# bare_bone_arduino.net
KiCad netlist of a schematic drawn in EAGLE
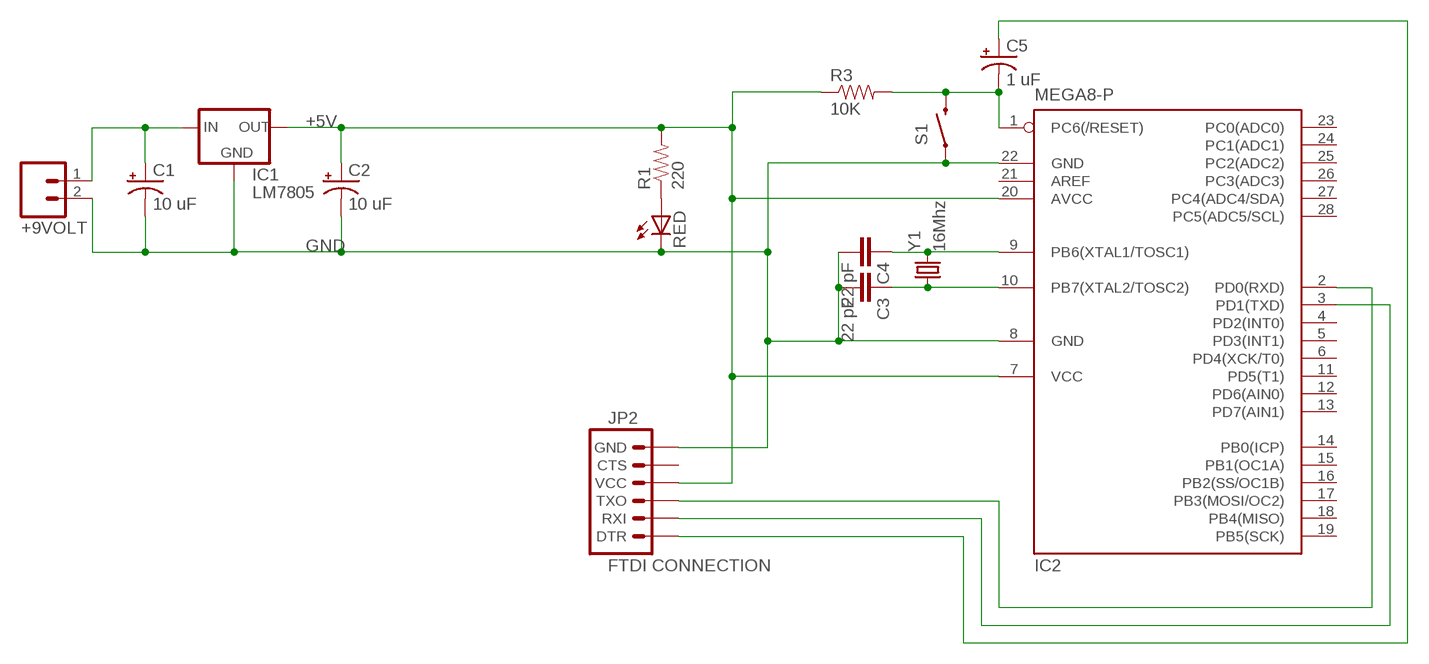
[diagram p0: schematic, sheet 1]

(export (version "E")
  (design (tool "Eeschema 10.0.6"))
  (components
    (comp (ref "+9VOLT")
      (value "M02PTH4")
      (footprint "eagle-import:1X02_XTRA_BIG")
      (libsource (lib "eagle-import") (part "M02PTH4"))
    )
    (comp (ref "C1")
      (value "10 uF")
      (footprint "eagle-import:VISHAY_C")
      (libsource (lib "eagle-import") (part "CAP_POLSMD"))
    )
    (comp (ref "C2")
      (value "10 uF")
      (footprint "eagle-import:VISHAY_C")
      (libsource (lib "eagle-import") (part "CAP_POLSMD"))
    )
    (comp (ref "C3")
      (value "22 pF")
      (footprint "eagle-import:CAP-PTH-5MM")
      (libsource (lib "eagle-import") (part "CAPPTH1"))
    )
    (comp (ref "C4")
      (value "22 pF")
      (footprint "eagle-import:CAP-PTH-5MM")
      (libsource (lib "eagle-import") (part "CAPPTH1"))
    )
    (comp (ref "C5")
      (value "1 uF")
      (footprint "eagle-import:CPOL-RADIAL-100UF-25V")
      (libsource (lib "eagle-import") (part "CAP_POLPTH1"))
    )
    (comp (ref "IC1")
      (value "LM7805")
      (footprint "eagle-import:TO-220-ALT")
      (libsource (lib "eagle-import") (part "V_REG_78XX-TO-220"))
    )
    (comp (ref "IC2")
      (value "MEGA8-P")
      (footprint "eagle-import:DIL28-3")
      (libsource (lib "eagle-import") (part "MEGA8-P"))
    )
    (comp (ref "JP2")
      (value "FTDI CONNECTION")
      (footprint "eagle-import:1X06")
      (libsource (lib "eagle-import") (part "ARDUINO_SERIAL_PROGRAMPTH"))
    )
    (comp (ref "R1")
      (value "220")
      (footprint "eagle-import:AXIAL-0.4")
      (libsource (lib "eagle-import") (part "RESISTORPTH-1/4W"))
    )
    (comp (ref "R3")
      (value "10K")
      (footprint "eagle-import:AXIAL-0.4")
      (libsource (lib "eagle-import") (part "RESISTORPTH-1/4W"))
    )
    (comp (ref "RED")
      (value "LED3MM")
      (footprint "eagle-import:LED3MM")
      (libsource (lib "eagle-import") (part "LED3MM"))
    )
    (comp (ref "S1")
      (value "SWITCH-MOMENTARY-2PTH")
      (footprint "eagle-import:TACTILE-PTH")
      (libsource (lib "eagle-import") (part "SWITCH-MOMENTARY-2PTH"))
    )
    (comp (ref "Y1")
      (value "16Mhz")
      (footprint "eagle-import:HC49US")
      (libsource (lib "eagle-import") (part "CRYSTALHC49US"))
    )
  )
  (nets
    (net (code "1") (name "/+5V") (class "Default")
      (node (ref "C2") (pin "+") (pinfunction "+_+") (pintype "passive"))
      (node (ref "IC1") (pin "OUT") (pinfunction "OUT_OUT") (pintype "output"))
      (node (ref "IC2") (pin "20") (pinfunction "AVCC_20") (pintype "power_in"))
      (node (ref "IC2") (pin "7") (pinfunction "VCC_7") (pintype "power_in"))
      (node (ref "JP2") (pin "4") (pinfunction "VCC_4") (pintype "passive"))
      (node (ref "R1") (pin "P$2") (pinfunction "2_P$2") (pintype "passive"))
      (node (ref "R3") (pin "P$1") (pinfunction "1_P$1") (pintype "passive"))
    )
    (net (code "2") (name "/GND") (class "Default")
      (node (ref "+9VOLT") (pin "2") (pinfunction "2_2") (pintype "passive"))
      (node (ref "C1") (pin "-") (pinfunction "-_-") (pintype "passive"))
      (node (ref "C2") (pin "-") (pinfunction "-_-") (pintype "passive"))
      (node (ref "C3") (pin "2") (pinfunction "2_2") (pintype "passive"))
      (node (ref "C4") (pin "2") (pinfunction "2_2") (pintype "passive"))
      (node (ref "IC1") (pin "GND") (pinfunction "GND_GND") (pintype "input"))
      (node (ref "IC2") (pin "22") (pinfunction "GND_22") (pintype "power_in"))
      (node (ref "IC2") (pin "8") (pinfunction "GND_8") (pintype "power_in"))
      (node (ref "JP2") (pin "6") (pinfunction "GND_6") (pintype "passive"))
      (node (ref "RED") (pin "K") (pinfunction "C_K") (pintype "passive"))
      (node (ref "S1") (pin "1") (pinfunction "1_1") (pintype "passive"))
    )
    (net (code "3") (name "Net-(+9VOLT-Pad1)") (class "Default")
      (node (ref "+9VOLT") (pin "1") (pinfunction "1_1") (pintype "passive"))
      (node (ref "C1") (pin "+") (pinfunction "+_+") (pintype "passive"))
      (node (ref "IC1") (pin "IN") (pinfunction "IN_IN") (pintype "input"))
    )
    (net (code "4") (name "Net-(C5-+)") (class "Default")
      (node (ref "C5") (pin "1") (pinfunction "+_1") (pintype "passive"))
      (node (ref "JP2") (pin "1") (pinfunction "DTR_1") (pintype "passive"))
    )
    (net (code "5") (name "Net-(C5--)") (class "Default")
      (node (ref "C5") (pin "2") (pinfunction "-_2") (pintype "passive"))
      (node (ref "IC2") (pin "1") (pinfunction "PC6(/RESET)_1") (pintype "bidirectional"))
      (node (ref "R3") (pin "P$2") (pinfunction "2_P$2") (pintype "passive"))
      (node (ref "S1") (pin "3") (pinfunction "2_3") (pintype "passive"))
    )
    (net (code "6") (name "Net-(IC2-PB6(XTAL1{slash}TOSC1))") (class "Default")
      (node (ref "C4") (pin "1") (pinfunction "1_1") (pintype "passive"))
      (node (ref "IC2") (pin "9") (pinfunction "PB6(XTAL1/TOSC1)_9") (pintype "bidirectional"))
      (node (ref "Y1") (pin "2") (pinfunction "2_2") (pintype "passive"))
    )
    (net (code "7") (name "Net-(IC2-PB7(XTAL2{slash}TOSC2))") (class "Default")
      (node (ref "C3") (pin "1") (pinfunction "1_1") (pintype "passive"))
      (node (ref "IC2") (pin "10") (pinfunction "PB7(XTAL2/TOSC2)_10") (pintype "bidirectional"))
      (node (ref "Y1") (pin "1") (pinfunction "1_1") (pintype "passive"))
    )
    (net (code "8") (name "Net-(IC2-PD0(RXD))") (class "Default")
      (node (ref "IC2") (pin "2") (pinfunction "PD0(RXD)_2") (pintype "bidirectional"))
      (node (ref "JP2") (pin "3") (pinfunction "TXO_3") (pintype "passive"))
    )
    (net (code "9") (name "Net-(IC2-PD1(TXD))") (class "Default")
      (node (ref "IC2") (pin "3") (pinfunction "PD1(TXD)_3") (pintype "bidirectional"))
      (node (ref "JP2") (pin "2") (pinfunction "RXI_2") (pintype "passive"))
    )
    (net (code "10") (name "Net-(R1-1)") (class "Default")
      (node (ref "R1") (pin "P$1") (pinfunction "1_P$1") (pintype "passive"))
      (node (ref "RED") (pin "A") (pinfunction "A_A") (pintype "passive"))
    )
    (net (code "11") (name "unconnected-(IC2-AREF-Pad21)") (class "Default")
      (node (ref "IC2") (pin "21") (pinfunction "AREF_21") (pintype "passive"))
    )
    (net (code "12") (name "unconnected-(IC2-PB0(ICP)-Pad14)") (class "Default")
      (node (ref "IC2") (pin "14") (pinfunction "PB0(ICP)_14") (pintype "bidirectional"))
    )
    (net (code "13") (name "unconnected-(IC2-PB1(OC1A)-Pad15)") (class "Default")
      (node (ref "IC2") (pin "15") (pinfunction "PB1(OC1A)_15") (pintype "bidirectional"))
    )
    (net (code "14") (name "unconnected-(IC2-PB2(SS{slash}OC1B)-Pad16)") (class "Default")
      (node (ref "IC2") (pin "16") (pinfunction "PB2(SS/OC1B)_16") (pintype "bidirectional"))
    )
    (net (code "15") (name "unconnected-(IC2-PB3(MOSI{slash}OC2)-Pad17)") (class "Default")
      (node (ref "IC2") (pin "17") (pinfunction "PB3(MOSI/OC2)_17") (pintype "bidirectional"))
    )
    (net (code "16") (name "unconnected-(IC2-PB4(MISO)-Pad18)") (class "Default")
      (node (ref "IC2") (pin "18") (pinfunction "PB4(MISO)_18") (pintype "bidirectional"))
    )
    (net (code "17") (name "unconnected-(IC2-PB5(SCK)-Pad19)") (class "Default")
      (node (ref "IC2") (pin "19") (pinfunction "PB5(SCK)_19") (pintype "bidirectional"))
    )
    (net (code "18") (name "unconnected-(IC2-PC0(ADC0)-Pad23)") (class "Default")
      (node (ref "IC2") (pin "23") (pinfunction "PC0(ADC0)_23") (pintype "bidirectional"))
    )
    (net (code "19") (name "unconnected-(IC2-PC1(ADC1)-Pad24)") (class "Default")
      (node (ref "IC2") (pin "24") (pinfunction "PC1(ADC1)_24") (pintype "bidirectional"))
    )
    (net (code "20") (name "unconnected-(IC2-PC2(ADC2)-Pad25)") (class "Default")
      (node (ref "IC2") (pin "25") (pinfunction "PC2(ADC2)_25") (pintype "bidirectional"))
    )
    (net (code "21") (name "unconnected-(IC2-PC3(ADC3)-Pad26)") (class "Default")
      (node (ref "IC2") (pin "26") (pinfunction "PC3(ADC3)_26") (pintype "bidirectional"))
    )
    (net (code "22") (name "unconnected-(IC2-PC4(ADC4{slash}SDA)-Pad27)") (class "Default")
      (node (ref "IC2") (pin "27") (pinfunction "PC4(ADC4/SDA)_27") (pintype "bidirectional"))
    )
    (net (code "23") (name "unconnected-(IC2-PC5(ADC5{slash}SCL)-Pad28)") (class "Default")
      (node (ref "IC2") (pin "28") (pinfunction "PC5(ADC5/SCL)_28") (pintype "bidirectional"))
    )
    (net (code "24") (name "unconnected-(IC2-PD2(INT0)-Pad4)") (class "Default")
      (node (ref "IC2") (pin "4") (pinfunction "PD2(INT0)_4") (pintype "bidirectional"))
    )
    (net (code "25") (name "unconnected-(IC2-PD3(INT1)-Pad5)") (class "Default")
      (node (ref "IC2") (pin "5") (pinfunction "PD3(INT1)_5") (pintype "bidirectional"))
    )
    (net (code "26") (name "unconnected-(IC2-PD4(XCK{slash}T0)-Pad6)") (class "Default")
      (node (ref "IC2") (pin "6") (pinfunction "PD4(XCK/T0)_6") (pintype "bidirectional"))
    )
    (net (code "27") (name "unconnected-(IC2-PD5(T1)-Pad11)") (class "Default")
      (node (ref "IC2") (pin "11") (pinfunction "PD5(T1)_11") (pintype "bidirectional"))
    )
    (net (code "28") (name "unconnected-(IC2-PD6(AIN0)-Pad12)") (class "Default")
      (node (ref "IC2") (pin "12") (pinfunction "PD6(AIN0)_12") (pintype "bidirectional"))
    )
    (net (code "29") (name "unconnected-(IC2-PD7(AIN1)-Pad13)") (class "Default")
      (node (ref "IC2") (pin "13") (pinfunction "PD7(AIN1)_13") (pintype "bidirectional"))
    )
    (net (code "30") (name "unconnected-(JP2-CTS-Pad5)") (class "Default")
      (node (ref "JP2") (pin "5") (pinfunction "CTS_5") (pintype "passive"))
    )
  )
)
